# AHT20_Sensor.net
KiCad netlist of a schematic drawn in Altium Designer
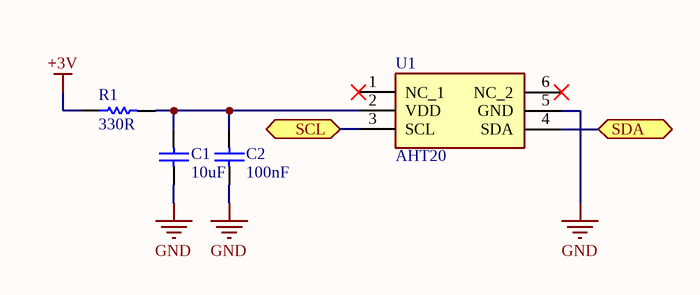
[diagram p0: AHT20_Sensor.SchDoc]

(export (version "E")
  (design (tool "Eeschema 10.0.6"))
  (components
    (comp (ref "C1")
      (value "10uF")
      (footprint "Wurth 0603 capacitor")
      (fields (field (name "Comment") "Generic Capacitor 10uF 0603"))
      (libsource (lib "Passives") (part "Generic Capacitor 10uF 0603"))
    )
    (comp (ref "C2")
      (value "100nF")
      (footprint "Wurth 0603 capacitor")
      (fields (field (name "Comment") "Generic Capacitor 100nF 0603"))
      (libsource (lib "Passives") (part "Generic Capacitor 100nF 0603"))
    )
    (comp (ref "R1")
      (value "330R")
      (footprint "Wurth 0603 Resistor")
      (fields (field (name "Comment") "Generic Resistor 330R 0603"))
      (libsource (lib "Passives") (part "Generic Resistor 330R 0603"))
    )
    (comp (ref "U1")
      (value "AHT20")
      (footprint "SamacSys:AHT20")
      (description "Undefined or Miscellaneous")
      (libsource (lib "*") (part "AHT20"))
    )
  )
  (nets
    (net (code "1") (name "+3V") (class "Default")
      (node (ref "R1") (pin "1") (pinfunction "1_1") (pintype "passive"))
    )
    (net (code "2") (name "/SCL") (class "Default")
      (node (ref "U1") (pin "3") (pinfunction "SCL_3") (pintype "passive"))
    )
    (net (code "3") (name "/SDA") (class "Default")
      (node (ref "U1") (pin "4") (pinfunction "SDA_4") (pintype "passive"))
    )
    (net (code "4") (name "GND") (class "Default")
      (node (ref "C1") (pin "1") (pinfunction "1_1") (pintype "passive"))
      (node (ref "C2") (pin "1") (pinfunction "1_1") (pintype "passive"))
      (node (ref "U1") (pin "5") (pinfunction "GND_5") (pintype "passive"))
    )
    (net (code "5") (name "Net-(U1-VDD)") (class "Default")
      (node (ref "C1") (pin "2") (pinfunction "2_2") (pintype "passive"))
      (node (ref "C2") (pin "2") (pinfunction "2_2") (pintype "passive"))
      (node (ref "R1") (pin "2") (pinfunction "2_2") (pintype "passive"))
      (node (ref "U1") (pin "2") (pinfunction "VDD_2") (pintype "passive"))
    )
    (net (code "6") (name "unconnected-(U1-NC_1-Pad1)") (class "Default")
      (node (ref "U1") (pin "1") (pinfunction "NC_1_1") (pintype "passive+no_connect"))
    )
    (net (code "7") (name "unconnected-(U1-NC_2-Pad6)") (class "Default")
      (node (ref "U1") (pin "6") (pinfunction "NC_2_6") (pintype "passive+no_connect"))
    )
  )
)
